# multiplier.net
KiCad netlist of a schematic drawn in Altium Designer
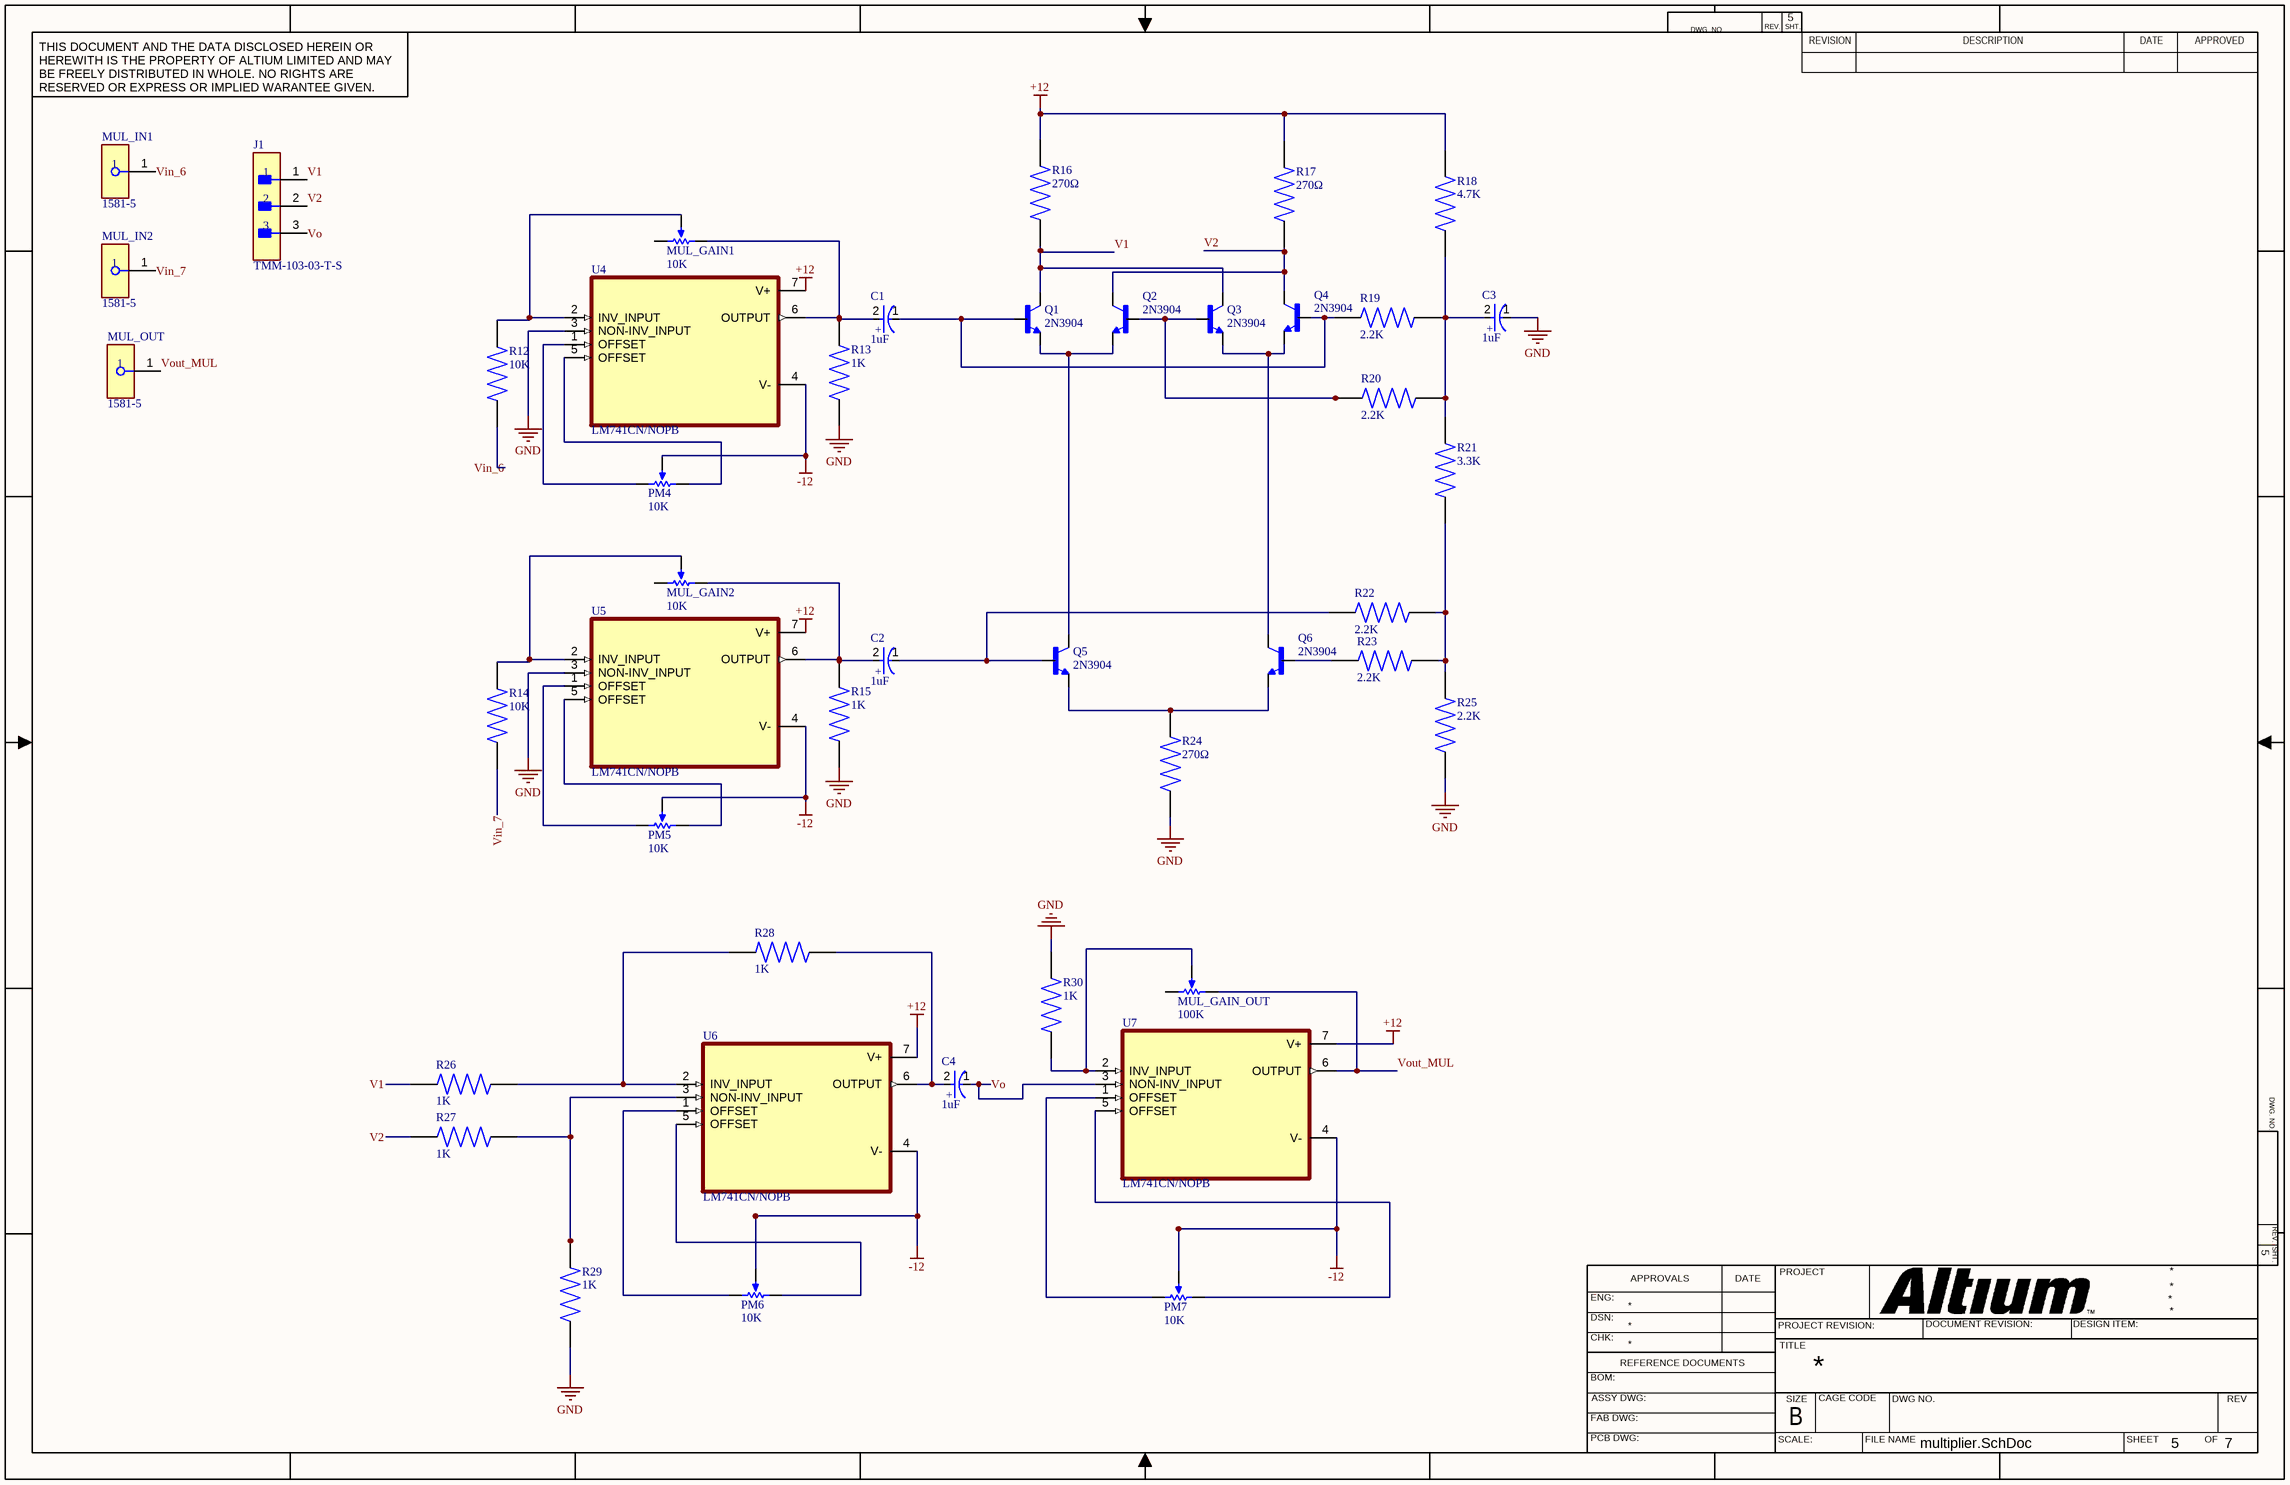
[diagram p0: multiplier.SchDoc]

(export (version "E")
  (design (tool "Eeschema 10.0.6"))
  (components
    (comp (ref "C1")
      (value "1uF")
      (footprint "FP-ECA-2CHG010I-MFG")
      (description "CAP ALUM 1UF 20% 160V RADIAL")
      (fields (field (name "TOLERANCE") "20%"))
      (libsource (lib "Altium Content Vault") (part "a00bbbee19879c290e62620ae7e47b1"))
    )
    (comp (ref "C2")
      (value "1uF")
      (footprint "FP-ECA-2CHG010I-MFG")
      (description "CAP ALUM 1UF 20% 160V RADIAL")
      (fields (field (name "TOLERANCE") "20%"))
      (libsource (lib "Altium Content Vault") (part "a00bbbee19879c290e62620ae7e47b1"))
    )
    (comp (ref "C3")
      (value "1uF")
      (footprint "FP-ECA-2CHG010I-MFG")
      (description "CAP ALUM 1UF 20% 160V RADIAL")
      (fields (field (name "TOLERANCE") "20%"))
      (libsource (lib "Altium Content Vault") (part "a00bbbee19879c290e62620ae7e47b1"))
    )
    (comp (ref "C4")
      (value "1uF")
      (footprint "FP-ECA-2CHG010I-MFG")
      (description "CAP ALUM 1UF 20% 160V RADIAL")
      (fields (field (name "TOLERANCE") "20%"))
      (libsource (lib "Altium Content Vault") (part "a00bbbee19879c290e62620ae7e47b1"))
    )
    (comp (ref "J1")
      (value "TMM-103-03-T-S")
      (footprint "FP-TMM-103-03-T-S-MFG")
      (description "CONN HEADER VERT 3POS 2MM")
      (libsource (lib "Altium Content Vault") (part "0d3f023dd272f625e17a2be33dea85f"))
    )
    (comp (ref "MUL_GAIN1")
      (value "10K")
      (footprint "PCBComponent_1")
      (libsource (lib "Integrated_Library1") (part "Component_1"))
    )
    (comp (ref "MUL_GAIN2")
      (value "10K")
      (footprint "PCBComponent_1")
      (libsource (lib "Integrated_Library1") (part "Component_1"))
    )
    (comp (ref "MUL_GAIN_OUT")
      (value "100K")
      (footprint "PCBComponent_1")
      (libsource (lib "Integrated_Library1") (part "Component_1"))
    )
    (comp (ref "MUL_IN1")
      (value "1581-5")
      (footprint "FP-1581-5-MFG")
      (description "CONN BANANA JACK TURRET GREEN")
      (libsource (lib "Altium Content Vault") (part "c5c826e0c4b67fe3b42ef77f2d4decc"))
    )
    (comp (ref "MUL_IN2")
      (value "1581-5")
      (footprint "FP-1581-5-MFG")
      (description "CONN BANANA JACK TURRET GREEN")
      (libsource (lib "Altium Content Vault") (part "c5c826e0c4b67fe3b42ef77f2d4decc"))
    )
    (comp (ref "MUL_OUT")
      (value "1581-5")
      (footprint "FP-1581-5-MFG")
      (description "CONN BANANA JACK TURRET GREEN")
      (libsource (lib "Altium Content Vault") (part "c5c826e0c4b67fe3b42ef77f2d4decc"))
    )
    (comp (ref "PM4")
      (value "10K")
      (footprint "PCBComponent_1")
      (libsource (lib "Integrated_Library1") (part "Component_1"))
    )
    (comp (ref "PM5")
      (value "10K")
      (footprint "PCBComponent_1")
      (libsource (lib "Integrated_Library1") (part "Component_1"))
    )
    (comp (ref "PM6")
      (value "10K")
      (footprint "PCBComponent_1")
      (libsource (lib "Integrated_Library1") (part "Component_1"))
    )
    (comp (ref "PM7")
      (value "10K")
      (footprint "PCBComponent_1")
      (libsource (lib "Integrated_Library1") (part "Component_1"))
    )
    (comp (ref "Q1")
      (value "2N3904")
      (footprint "TO92254P460H750-3")
      (description "BJT, TO-92, 40V, 200mA, NPN, 0.625W, 150Â°C")
      (fields (field (name "MF") "Diotec Semiconductor"))
      (libsource (lib "") (part "2N3904_1"))
    )
    (comp (ref "Q2")
      (value "2N3904")
      (footprint "TO92254P460H750-3")
      (description "BJT, TO-92, 40V, 200mA, NPN, 0.625W, 150Â°C")
      (fields (field (name "MF") "Diotec Semiconductor"))
      (libsource (lib "2N3904") (part "2N3904"))
    )
    (comp (ref "Q3")
      (value "2N3904")
      (footprint "TO92254P460H750-3")
      (description "BJT, TO-92, 40V, 200mA, NPN, 0.625W, 150Â°C")
      (fields (field (name "MF") "Diotec Semiconductor"))
      (libsource (lib "") (part "2N3904_1"))
    )
    (comp (ref "Q4")
      (value "2N3904")
      (footprint "TO92254P460H750-3")
      (description "BJT, TO-92, 40V, 200mA, NPN, 0.625W, 150Â°C")
      (fields (field (name "MF") "Diotec Semiconductor"))
      (libsource (lib "2N3904") (part "2N3904"))
    )
    (comp (ref "Q5")
      (value "2N3904")
      (footprint "TO92254P460H750-3")
      (description "BJT, TO-92, 40V, 200mA, NPN, 0.625W, 150Â°C")
      (fields (field (name "MF") "Diotec Semiconductor"))
      (libsource (lib "") (part "2N3904_1"))
    )
    (comp (ref "Q6")
      (value "2N3904")
      (footprint "TO92254P460H750-3")
      (description "BJT, TO-92, 40V, 200mA, NPN, 0.625W, 150Â°C")
      (fields (field (name "MF") "Diotec Semiconductor"))
      (libsource (lib "2N3904") (part "2N3904"))
    )
    (comp (ref "R12")
      (value "10K")
      (footprint "RESAD1100W55L680D260")
      (description "1.07 kOhms Â±1% 0.25W, 1/4W Through Hole Resistor Axial - Metal Film")
      (fields (field (name "MF") "Yageo") (field (name "MP") "MFR-25FBF52-1K"))
      (libsource (lib "MFR-25FBF52-1K") (part "MFR-25FBF52-1K"))
    )
    (comp (ref "R13")
      (value "1K")
      (footprint "RESAD1100W55L680D260")
      (description "1.07 kOhms Â±1% 0.25W, 1/4W Through Hole Resistor Axial - Metal Film")
      (fields (field (name "MF") "Yageo") (field (name "MP") "MFR-25FBF52-1K"))
      (libsource (lib "MFR-25FBF52-1K") (part "MFR-25FBF52-1K"))
    )
    (comp (ref "R14")
      (value "10K")
      (footprint "RESAD1100W55L680D260")
      (description "1.07 kOhms Â±1% 0.25W, 1/4W Through Hole Resistor Axial - Metal Film")
      (fields (field (name "MF") "Yageo") (field (name "MP") "MFR-25FBF52-1K"))
      (libsource (lib "MFR-25FBF52-1K") (part "MFR-25FBF52-1K"))
    )
    (comp (ref "R15")
      (value "1K")
      (footprint "RESAD1100W55L680D260")
      (description "1.07 kOhms Â±1% 0.25W, 1/4W Through Hole Resistor Axial - Metal Film")
      (fields (field (name "MF") "Yageo") (field (name "MP") "MFR-25FBF52-1K"))
      (libsource (lib "MFR-25FBF52-1K") (part "MFR-25FBF52-1K"))
    )
    (comp (ref "R16")
      (value "270Ω")
      (footprint "RESAD1100W55L680D260")
      (description "1.07 kOhms Â±1% 0.25W, 1/4W Through Hole Resistor Axial - Metal Film")
      (fields (field (name "MF") "Yageo") (field (name "MP") "MFR-25FBF52-1K"))
      (libsource (lib "MFR-25FBF52-1K") (part "MFR-25FBF52-1K"))
    )
    (comp (ref "R17")
      (value "270Ω")
      (footprint "RESAD1100W55L680D260")
      (description "1.07 kOhms Â±1% 0.25W, 1/4W Through Hole Resistor Axial - Metal Film")
      (fields (field (name "MF") "Yageo") (field (name "MP") "MFR-25FBF52-1K"))
      (libsource (lib "MFR-25FBF52-1K") (part "MFR-25FBF52-1K"))
    )
    (comp (ref "R18")
      (value "4.7K")
      (footprint "RESAD1100W55L680D260")
      (description "1.07 kOhms Â±1% 0.25W, 1/4W Through Hole Resistor Axial - Metal Film")
      (fields (field (name "MF") "Yageo") (field (name "MP") "MFR-25FBF52-1K"))
      (libsource (lib "MFR-25FBF52-1K") (part "MFR-25FBF52-1K"))
    )
    (comp (ref "R19")
      (value "2.2K")
      (footprint "RESAD1100W55L680D260")
      (description "1.07 kOhms Â±1% 0.25W, 1/4W Through Hole Resistor Axial - Metal Film")
      (fields (field (name "MF") "Yageo") (field (name "MP") "MFR-25FBF52-1K"))
      (libsource (lib "MFR-25FBF52-1K") (part "MFR-25FBF52-1K"))
    )
    (comp (ref "R20")
      (value "2.2K")
      (footprint "RESAD1100W55L680D260")
      (description "1.07 kOhms Â±1% 0.25W, 1/4W Through Hole Resistor Axial - Metal Film")
      (fields (field (name "MF") "Yageo") (field (name "MP") "MFR-25FBF52-1K"))
      (libsource (lib "MFR-25FBF52-1K") (part "MFR-25FBF52-1K"))
    )
    (comp (ref "R21")
      (value "3.3K")
      (footprint "RESAD1100W55L680D260")
      (description "1.07 kOhms Â±1% 0.25W, 1/4W Through Hole Resistor Axial - Metal Film")
      (fields (field (name "MF") "Yageo") (field (name "MP") "MFR-25FBF52-1K"))
      (libsource (lib "MFR-25FBF52-1K") (part "MFR-25FBF52-1K"))
    )
    (comp (ref "R22")
      (value "2.2K")
      (footprint "RESAD1100W55L680D260")
      (description "1.07 kOhms Â±1% 0.25W, 1/4W Through Hole Resistor Axial - Metal Film")
      (fields (field (name "MF") "Yageo") (field (name "MP") "MFR-25FBF52-1K"))
      (libsource (lib "MFR-25FBF52-1K") (part "MFR-25FBF52-1K"))
    )
    (comp (ref "R23")
      (value "2.2K")
      (footprint "RESAD1100W55L680D260")
      (description "1.07 kOhms Â±1% 0.25W, 1/4W Through Hole Resistor Axial - Metal Film")
      (fields (field (name "MF") "Yageo") (field (name "MP") "MFR-25FBF52-1K"))
      (libsource (lib "MFR-25FBF52-1K") (part "MFR-25FBF52-1K"))
    )
    (comp (ref "R24")
      (value "270Ω")
      (footprint "RESAD1100W55L680D260")
      (description "1.07 kOhms Â±1% 0.25W, 1/4W Through Hole Resistor Axial - Metal Film")
      (fields (field (name "MF") "Yageo") (field (name "MP") "MFR-25FBF52-1K"))
      (libsource (lib "MFR-25FBF52-1K") (part "MFR-25FBF52-1K"))
    )
    (comp (ref "R25")
      (value "2.2K")
      (footprint "RESAD1100W55L680D260")
      (description "1.07 kOhms Â±1% 0.25W, 1/4W Through Hole Resistor Axial - Metal Film")
      (fields (field (name "MF") "Yageo") (field (name "MP") "MFR-25FBF52-1K"))
      (libsource (lib "MFR-25FBF52-1K") (part "MFR-25FBF52-1K"))
    )
    (comp (ref "R26")
      (value "1K")
      (footprint "RESAD1100W55L680D260")
      (description "1.07 kOhms Â±1% 0.25W, 1/4W Through Hole Resistor Axial - Metal Film")
      (fields (field (name "MF") "Yageo") (field (name "MP") "MFR-25FBF52-1K"))
      (libsource (lib "MFR-25FBF52-1K") (part "MFR-25FBF52-1K"))
    )
    (comp (ref "R27")
      (value "1K")
      (footprint "RESAD1100W55L680D260")
      (description "1.07 kOhms Â±1% 0.25W, 1/4W Through Hole Resistor Axial - Metal Film")
      (fields (field (name "MF") "Yageo") (field (name "MP") "MFR-25FBF52-1K"))
      (libsource (lib "MFR-25FBF52-1K") (part "MFR-25FBF52-1K"))
    )
    (comp (ref "R28")
      (value "1K")
      (footprint "RESAD1100W55L680D260")
      (description "1.07 kOhms Â±1% 0.25W, 1/4W Through Hole Resistor Axial - Metal Film")
      (fields (field (name "MF") "Yageo") (field (name "MP") "MFR-25FBF52-1K"))
      (libsource (lib "MFR-25FBF52-1K") (part "MFR-25FBF52-1K"))
    )
    (comp (ref "R29")
      (value "1K")
      (footprint "RESAD1100W55L680D260")
      (description "1.07 kOhms Â±1% 0.25W, 1/4W Through Hole Resistor Axial - Metal Film")
      (fields (field (name "MF") "Yageo") (field (name "MP") "MFR-25FBF52-1K"))
      (libsource (lib "MFR-25FBF52-1K") (part "MFR-25FBF52-1K"))
    )
    (comp (ref "R30")
      (value "1K")
      (footprint "RESAD1100W55L680D260")
      (description "1.07 kOhms Â±1% 0.25W, 1/4W Through Hole Resistor Axial - Metal Film")
      (fields (field (name "MF") "Yageo") (field (name "MP") "MFR-25FBF52-1K"))
      (libsource (lib "MFR-25FBF52-1K") (part "MFR-25FBF52-1K"))
    )
    (comp (ref "U4")
      (value "LM741CN/NOPB")
      (footprint "DIP794W45P254L959H508Q8")
      (description "Single, 44-V, 1-MHz operational amplifier")
      (fields (field (name "MF") "Texas Instruments"))
      (libsource (lib "LM741CN_NOPB (1)") (part "LM741CN/NOPB"))
    )
    (comp (ref "U5")
      (value "LM741CN/NOPB")
      (footprint "DIP794W45P254L959H508Q8")
      (description "Single, 44-V, 1-MHz operational amplifier")
      (fields (field (name "MF") "Texas Instruments"))
      (libsource (lib "LM741CN_NOPB (1)") (part "LM741CN/NOPB"))
    )
    (comp (ref "U6")
      (value "LM741CN/NOPB")
      (footprint "DIP794W45P254L959H508Q8")
      (description "Single, 44-V, 1-MHz operational amplifier")
      (fields (field (name "MF") "Texas Instruments"))
      (libsource (lib "LM741CN_NOPB (1)") (part "LM741CN/NOPB"))
    )
    (comp (ref "U7")
      (value "LM741CN/NOPB")
      (footprint "DIP794W45P254L959H508Q8")
      (description "Single, 44-V, 1-MHz operational amplifier")
      (fields (field (name "MF") "Texas Instruments"))
      (libsource (lib "LM741CN_NOPB (1)") (part "LM741CN/NOPB"))
    )
  )
  (nets
    (net (code "1") (name "+12") (class "Default")
      (node (ref "R16") (pin "2") (pinfunction "2_2") (pintype "passive"))
      (node (ref "R17") (pin "2") (pinfunction "2_2") (pintype "passive"))
      (node (ref "R18") (pin "2") (pinfunction "2_2") (pintype "passive"))
      (node (ref "U4") (pin "7") (pinfunction "V+_7") (pintype "power_in"))
      (node (ref "U5") (pin "7") (pinfunction "V+_7") (pintype "power_in"))
      (node (ref "U6") (pin "7") (pinfunction "V+_7") (pintype "power_in"))
      (node (ref "U7") (pin "7") (pinfunction "V+_7") (pintype "power_in"))
    )
    (net (code "2") (name "-12") (class "Default")
      (node (ref "PM4") (pin "2") (pinfunction "S_2") (pintype "passive"))
      (node (ref "PM5") (pin "2") (pinfunction "S_2") (pintype "passive"))
      (node (ref "PM6") (pin "2") (pinfunction "S_2") (pintype "passive"))
      (node (ref "PM7") (pin "2") (pinfunction "S_2") (pintype "passive"))
      (node (ref "U4") (pin "4") (pinfunction "V-_4") (pintype "power_in"))
      (node (ref "U5") (pin "4") (pinfunction "V-_4") (pintype "power_in"))
      (node (ref "U6") (pin "4") (pinfunction "V-_4") (pintype "power_in"))
      (node (ref "U7") (pin "4") (pinfunction "V-_4") (pintype "power_in"))
    )
    (net (code "3") (name "/V1") (class "Default")
      (node (ref "J1") (pin "1") (pinfunction "1_1") (pintype "passive"))
      (node (ref "Q1") (pin "3") (pinfunction "C_3") (pintype "passive"))
      (node (ref "Q3") (pin "3") (pinfunction "C_3") (pintype "passive"))
      (node (ref "R16") (pin "1") (pinfunction "1_1") (pintype "passive"))
      (node (ref "R26") (pin "1") (pinfunction "1_1") (pintype "passive"))
    )
    (net (code "4") (name "/V2") (class "Default")
      (node (ref "J1") (pin "2") (pinfunction "2_2") (pintype "passive"))
      (node (ref "Q2") (pin "3") (pinfunction "C_3") (pintype "passive"))
      (node (ref "Q4") (pin "3") (pinfunction "C_3") (pintype "passive"))
      (node (ref "R17") (pin "1") (pinfunction "1_1") (pintype "passive"))
      (node (ref "R27") (pin "1") (pinfunction "1_1") (pintype "passive"))
    )
    (net (code "5") (name "/Vin_6") (class "Default")
      (node (ref "MUL_IN1") (pin "1") (pinfunction "1_1") (pintype "passive"))
      (node (ref "R12") (pin "1") (pinfunction "1_1") (pintype "passive"))
    )
    (net (code "6") (name "/Vin_7") (class "Default")
      (node (ref "MUL_IN2") (pin "1") (pinfunction "1_1") (pintype "passive"))
      (node (ref "R14") (pin "1") (pinfunction "1_1") (pintype "passive"))
    )
    (net (code "7") (name "/Vo") (class "Default")
      (node (ref "C4") (pin "1") (pinfunction "C_1") (pintype "passive"))
      (node (ref "J1") (pin "3") (pinfunction "3_3") (pintype "passive"))
      (node (ref "U7") (pin "3") (pinfunction "NON-INV_INPUT_3") (pintype "input"))
    )
    (net (code "8") (name "/Vout_MUL") (class "Default")
      (node (ref "MUL_GAIN_OUT") (pin "1") (pinfunction "CCW_1") (pintype "passive"))
      (node (ref "MUL_OUT") (pin "1") (pinfunction "1_1") (pintype "passive"))
      (node (ref "U7") (pin "6") (pinfunction "OUTPUT_6") (pintype "output"))
    )
    (net (code "9") (name "GND") (class "Default")
      (node (ref "C3") (pin "1") (pinfunction "C_1") (pintype "passive"))
      (node (ref "R13") (pin "1") (pinfunction "1_1") (pintype "passive"))
      (node (ref "R15") (pin "1") (pinfunction "1_1") (pintype "passive"))
      (node (ref "R24") (pin "1") (pinfunction "1_1") (pintype "passive"))
      (node (ref "R25") (pin "1") (pinfunction "1_1") (pintype "passive"))
      (node (ref "R29") (pin "1") (pinfunction "1_1") (pintype "passive"))
      (node (ref "R30") (pin "1") (pinfunction "1_1") (pintype "passive"))
      (node (ref "U4") (pin "3") (pinfunction "NON-INV_INPUT_3") (pintype "input"))
      (node (ref "U5") (pin "3") (pinfunction "NON-INV_INPUT_3") (pintype "input"))
    )
    (net (code "10") (name "Net-(C1-A)") (class "Default")
      (node (ref "C1") (pin "2") (pinfunction "A_2") (pintype "passive"))
      (node (ref "MUL_GAIN1") (pin "1") (pinfunction "CCW_1") (pintype "passive"))
      (node (ref "R13") (pin "2") (pinfunction "2_2") (pintype "passive"))
      (node (ref "U4") (pin "6") (pinfunction "OUTPUT_6") (pintype "output"))
    )
    (net (code "11") (name "Net-(C1-C)") (class "Default")
      (node (ref "C1") (pin "1") (pinfunction "C_1") (pintype "passive"))
      (node (ref "Q1") (pin "2") (pinfunction "B_2") (pintype "passive"))
      (node (ref "Q4") (pin "2") (pinfunction "B_2") (pintype "passive"))
      (node (ref "R19") (pin "1") (pinfunction "1_1") (pintype "passive"))
    )
    (net (code "12") (name "Net-(C2-A)") (class "Default")
      (node (ref "C2") (pin "2") (pinfunction "A_2") (pintype "passive"))
      (node (ref "MUL_GAIN2") (pin "1") (pinfunction "CCW_1") (pintype "passive"))
      (node (ref "R15") (pin "2") (pinfunction "2_2") (pintype "passive"))
      (node (ref "U5") (pin "6") (pinfunction "OUTPUT_6") (pintype "output"))
    )
    (net (code "13") (name "Net-(C2-C)") (class "Default")
      (node (ref "C2") (pin "1") (pinfunction "C_1") (pintype "passive"))
      (node (ref "Q5") (pin "2") (pinfunction "B_2") (pintype "passive"))
      (node (ref "R22") (pin "1") (pinfunction "1_1") (pintype "passive"))
    )
    (net (code "14") (name "Net-(C3-A)") (class "Default")
      (node (ref "C3") (pin "2") (pinfunction "A_2") (pintype "passive"))
      (node (ref "R18") (pin "1") (pinfunction "1_1") (pintype "passive"))
      (node (ref "R19") (pin "2") (pinfunction "2_2") (pintype "passive"))
      (node (ref "R20") (pin "2") (pinfunction "2_2") (pintype "passive"))
      (node (ref "R21") (pin "2") (pinfunction "2_2") (pintype "passive"))
    )
    (net (code "15") (name "Net-(C4-A)") (class "Default")
      (node (ref "C4") (pin "2") (pinfunction "A_2") (pintype "passive"))
      (node (ref "R28") (pin "2") (pinfunction "2_2") (pintype "passive"))
      (node (ref "U6") (pin "6") (pinfunction "OUTPUT_6") (pintype "output"))
    )
    (net (code "16") (name "Net-(MUL_GAIN1-S)") (class "Default")
      (node (ref "MUL_GAIN1") (pin "2") (pinfunction "S_2") (pintype "passive"))
      (node (ref "R12") (pin "2") (pinfunction "2_2") (pintype "passive"))
      (node (ref "U4") (pin "2") (pinfunction "INV_INPUT_2") (pintype "input"))
    )
    (net (code "17") (name "Net-(MUL_GAIN2-S)") (class "Default")
      (node (ref "MUL_GAIN2") (pin "2") (pinfunction "S_2") (pintype "passive"))
      (node (ref "R14") (pin "2") (pinfunction "2_2") (pintype "passive"))
      (node (ref "U5") (pin "2") (pinfunction "INV_INPUT_2") (pintype "input"))
    )
    (net (code "18") (name "Net-(MUL_GAIN_OUT-S)") (class "Default")
      (node (ref "MUL_GAIN_OUT") (pin "2") (pinfunction "S_2") (pintype "passive"))
      (node (ref "R30") (pin "2") (pinfunction "2_2") (pintype "passive"))
      (node (ref "U7") (pin "2") (pinfunction "INV_INPUT_2") (pintype "input"))
    )
    (net (code "19") (name "Net-(PM4-CCW)") (class "Default")
      (node (ref "PM4") (pin "1") (pinfunction "CCW_1") (pintype "passive"))
      (node (ref "U4") (pin "5") (pinfunction "OFFSET_5") (pintype "input"))
    )
    (net (code "20") (name "Net-(PM4-CW)") (class "Default")
      (node (ref "PM4") (pin "3") (pinfunction "CW_3") (pintype "passive"))
      (node (ref "U4") (pin "1") (pinfunction "OFFSET_1") (pintype "input"))
    )
    (net (code "21") (name "Net-(PM5-CCW)") (class "Default")
      (node (ref "PM5") (pin "1") (pinfunction "CCW_1") (pintype "passive"))
      (node (ref "U5") (pin "5") (pinfunction "OFFSET_5") (pintype "input"))
    )
    (net (code "22") (name "Net-(PM5-CW)") (class "Default")
      (node (ref "PM5") (pin "3") (pinfunction "CW_3") (pintype "passive"))
      (node (ref "U5") (pin "1") (pinfunction "OFFSET_1") (pintype "input"))
    )
    (net (code "23") (name "Net-(PM6-CCW)") (class "Default")
      (node (ref "PM6") (pin "1") (pinfunction "CCW_1") (pintype "passive"))
      (node (ref "U6") (pin "5") (pinfunction "OFFSET_5") (pintype "input"))
    )
    (net (code "24") (name "Net-(PM6-CW)") (class "Default")
      (node (ref "PM6") (pin "3") (pinfunction "CW_3") (pintype "passive"))
      (node (ref "U6") (pin "1") (pinfunction "OFFSET_1") (pintype "input"))
    )
    (net (code "25") (name "Net-(PM7-CCW)") (class "Default")
      (node (ref "PM7") (pin "1") (pinfunction "CCW_1") (pintype "passive"))
      (node (ref "U7") (pin "5") (pinfunction "OFFSET_5") (pintype "input"))
    )
    (net (code "26") (name "Net-(PM7-CW)") (class "Default")
      (node (ref "PM7") (pin "3") (pinfunction "CW_3") (pintype "passive"))
      (node (ref "U7") (pin "1") (pinfunction "OFFSET_1") (pintype "input"))
    )
    (net (code "27") (name "Net-(Q1-E)") (class "Default")
      (node (ref "Q1") (pin "1") (pinfunction "E_1") (pintype "passive"))
      (node (ref "Q2") (pin "1") (pinfunction "E_1") (pintype "passive"))
      (node (ref "Q5") (pin "3") (pinfunction "C_3") (pintype "passive"))
    )
    (net (code "28") (name "Net-(Q2-B)") (class "Default")
      (node (ref "Q2") (pin "2") (pinfunction "B_2") (pintype "passive"))
      (node (ref "Q3") (pin "2") (pinfunction "B_2") (pintype "passive"))
      (node (ref "R20") (pin "1") (pinfunction "1_1") (pintype "passive"))
    )
    (net (code "29") (name "Net-(Q3-E)") (class "Default")
      (node (ref "Q3") (pin "1") (pinfunction "E_1") (pintype "passive"))
      (node (ref "Q4") (pin "1") (pinfunction "E_1") (pintype "passive"))
      (node (ref "Q6") (pin "3") (pinfunction "C_3") (pintype "passive"))
    )
    (net (code "30") (name "Net-(Q5-E)") (class "Default")
      (node (ref "Q5") (pin "1") (pinfunction "E_1") (pintype "passive"))
      (node (ref "Q6") (pin "1") (pinfunction "E_1") (pintype "passive"))
      (node (ref "R24") (pin "2") (pinfunction "2_2") (pintype "passive"))
    )
    (net (code "31") (name "Net-(Q6-B)") (class "Default")
      (node (ref "Q6") (pin "2") (pinfunction "B_2") (pintype "passive"))
      (node (ref "R23") (pin "1") (pinfunction "1_1") (pintype "passive"))
    )
    (net (code "32") (name "Net-(R21-Pad1)") (class "Default")
      (node (ref "R21") (pin "1") (pinfunction "1_1") (pintype "passive"))
      (node (ref "R22") (pin "2") (pinfunction "2_2") (pintype "passive"))
      (node (ref "R23") (pin "2") (pinfunction "2_2") (pintype "passive"))
      (node (ref "R25") (pin "2") (pinfunction "2_2") (pintype "passive"))
    )
    (net (code "33") (name "Net-(U6-INV_INPUT)") (class "Default")
      (node (ref "R26") (pin "2") (pinfunction "2_2") (pintype "passive"))
      (node (ref "R28") (pin "1") (pinfunction "1_1") (pintype "passive"))
      (node (ref "U6") (pin "2") (pinfunction "INV_INPUT_2") (pintype "input"))
    )
    (net (code "34") (name "Net-(U6-NON-INV_INPUT)") (class "Default")
      (node (ref "R27") (pin "2") (pinfunction "2_2") (pintype "passive"))
      (node (ref "R29") (pin "2") (pinfunction "2_2") (pintype "passive"))
      (node (ref "U6") (pin "3") (pinfunction "NON-INV_INPUT_3") (pintype "input"))
    )
    (net (code "35") (name "unconnected-(MUL_GAIN1-CW-Pad3)") (class "Default")
      (node (ref "MUL_GAIN1") (pin "3") (pinfunction "CW_3") (pintype "passive"))
    )
    (net (code "36") (name "unconnected-(MUL_GAIN2-CW-Pad3)") (class "Default")
      (node (ref "MUL_GAIN2") (pin "3") (pinfunction "CW_3") (pintype "passive"))
    )
    (net (code "37") (name "unconnected-(MUL_GAIN_OUT-CW-Pad3)") (class "Default")
      (node (ref "MUL_GAIN_OUT") (pin "3") (pinfunction "CW_3") (pintype "passive"))
    )
  )
)
